# 1-Schematic_power_supply.net
KiCad netlist of a schematic drawn in EasyEDA
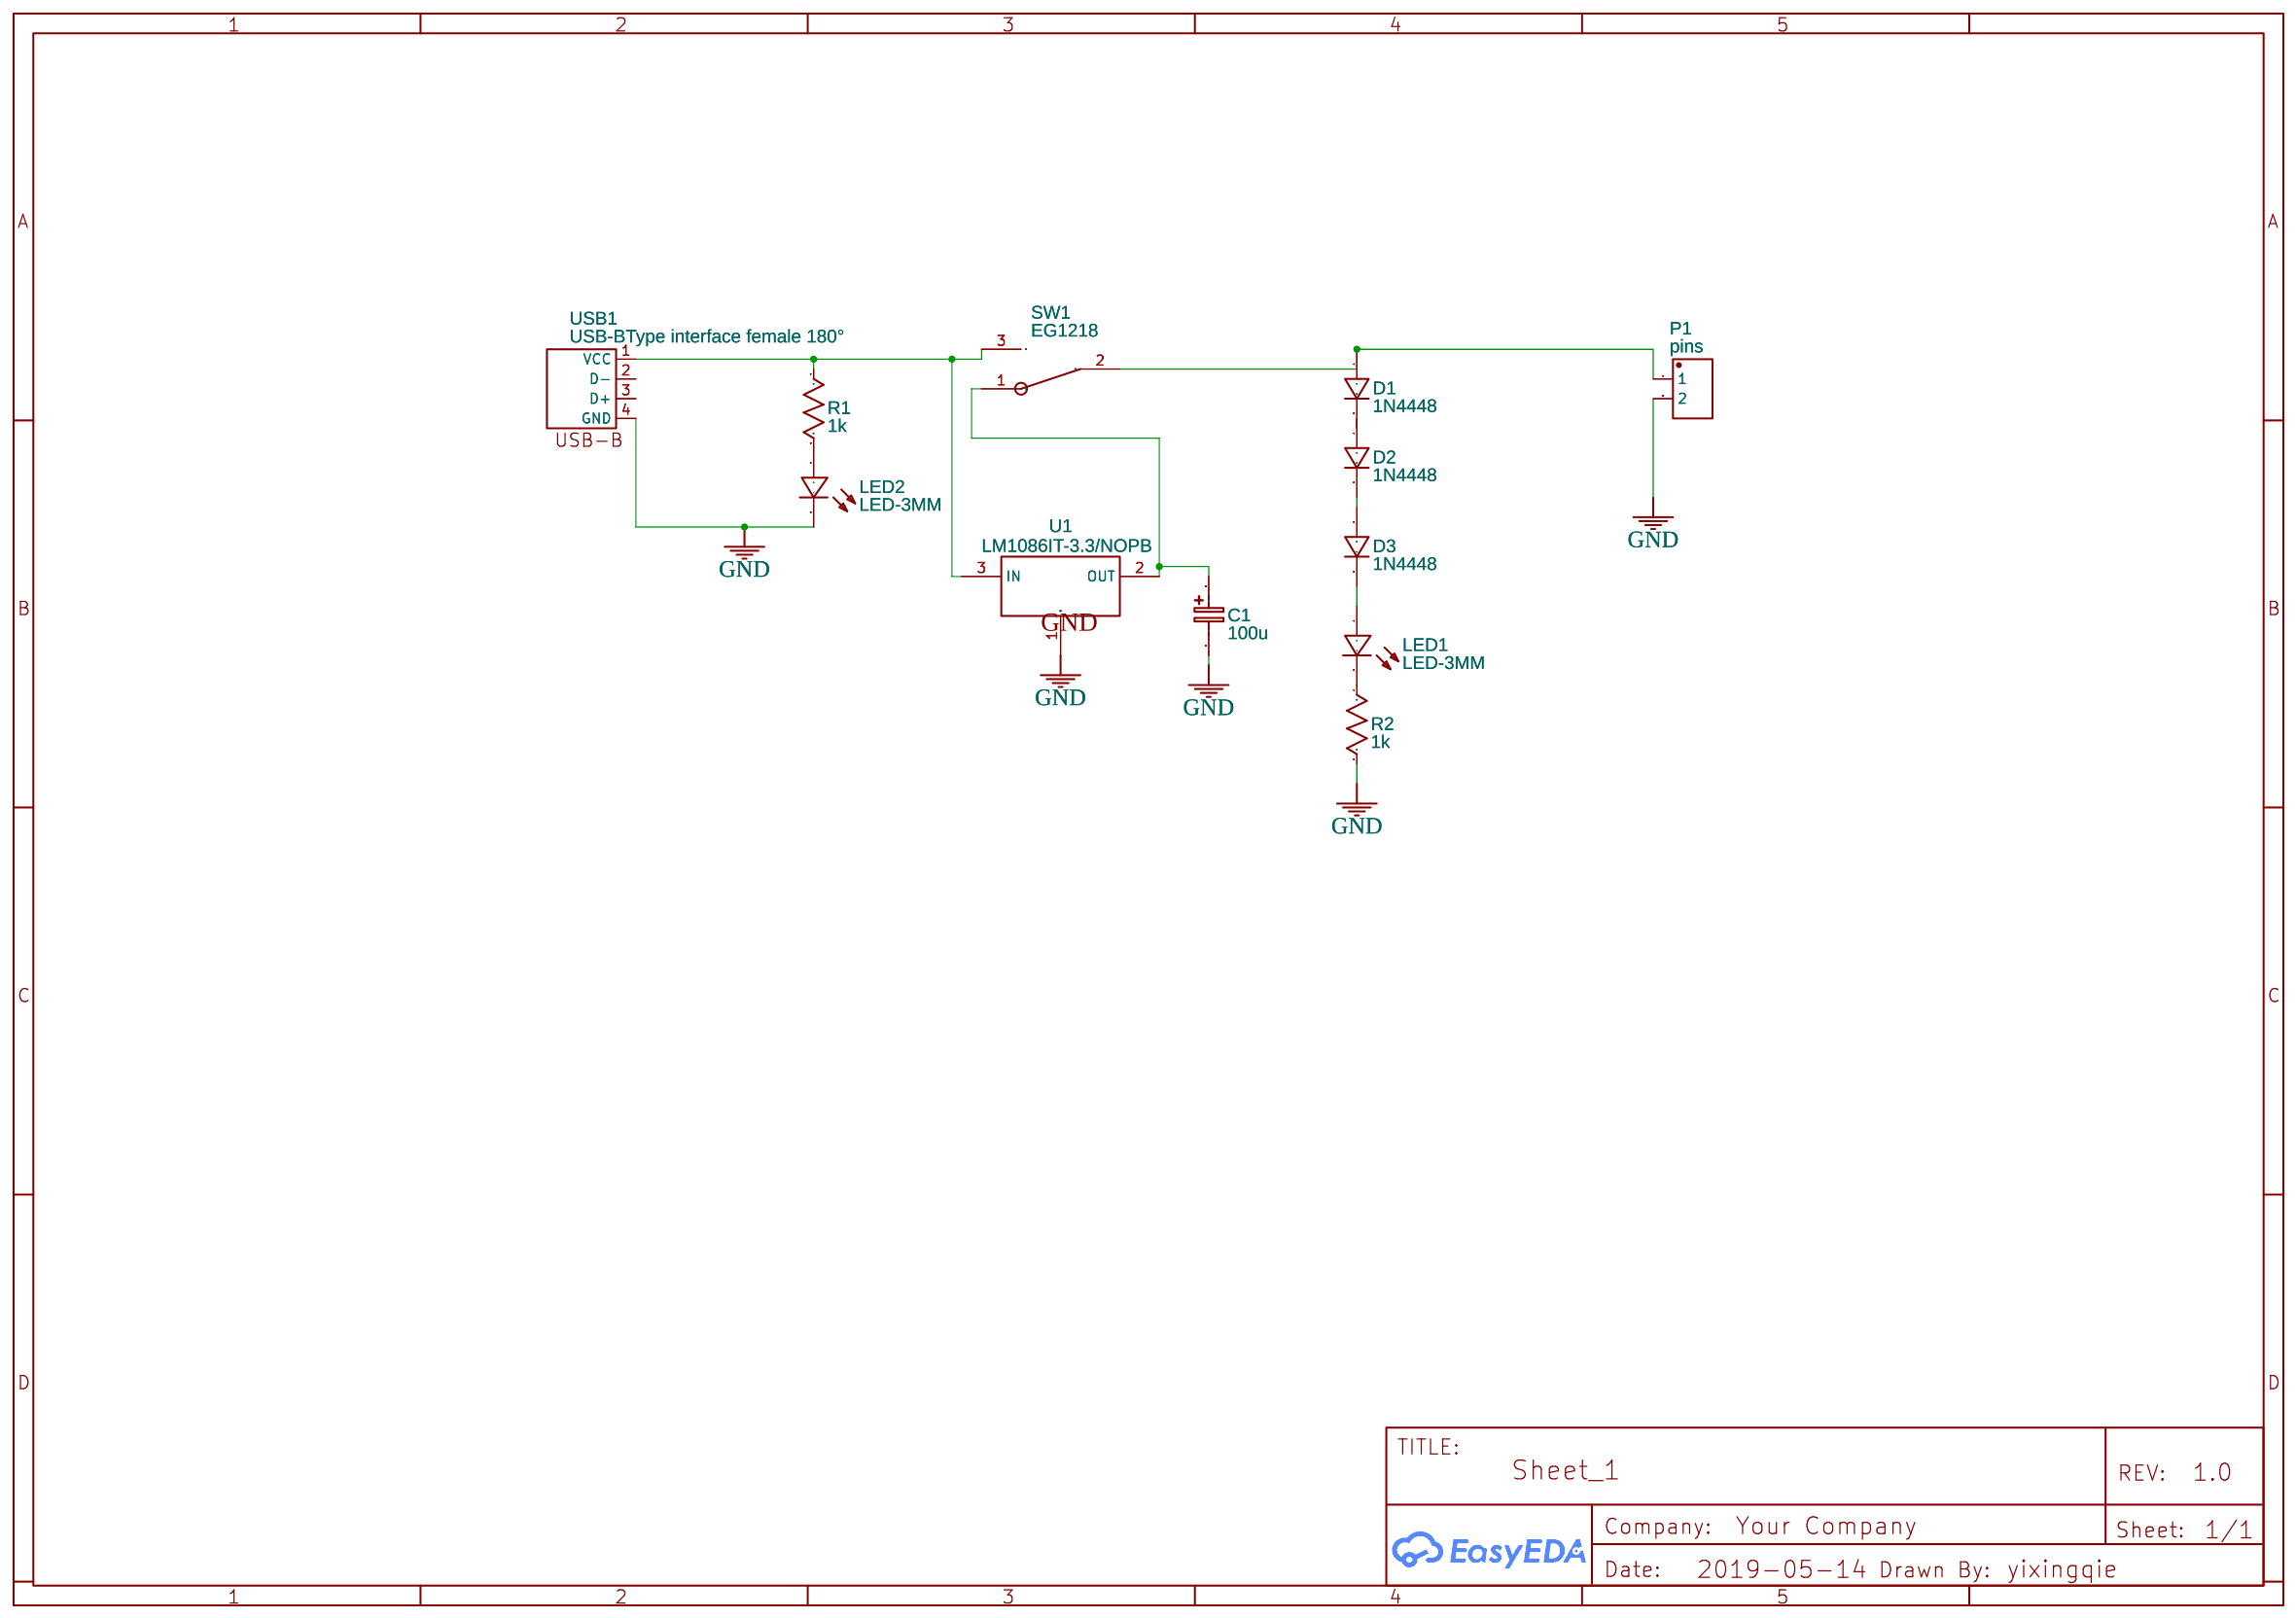
[diagram p0: schematic sheet]

(export (version "E")
  (design (tool "Eeschema 10.0.6"))
  (components
    (comp (ref "C1")
      (value "100u")
      (fields (field (name "BOM_Manufacturer Part") "?"))
      (libsource (lib "") (part "Cap_Electrolytic(TH)_D3.0XF1.5_EU"))
    )
    (comp (ref "D1")
      (value "1N4448")
      (fields (field (name "BOM_Supplier Part") "C54037"))
      (libsource (lib "") (part "Unknown_680_190"))
    )
    (comp (ref "D2")
      (value "1N4448")
      (fields (field (name "BOM_Supplier Part") "C54037"))
      (libsource (lib "") (part "Unknown_680_225"))
    )
    (comp (ref "D3")
      (value "1N4448")
      (fields (field (name "BOM_Supplier Part") "C54037"))
      (libsource (lib "") (part "Unknown_680_270"))
    )
    (comp (ref "LED1")
      (value "LED-3MM")
      (fields
        (field (name "BOM_Manufacturer Part") "204-10SURD/S530-A3")
        (field (name "BOM_Supplier Part") "C99772")
      )
      (libsource (lib "") (part "Unknown_680_320"))
    )
    (comp (ref "LED2")
      (value "LED-3MM")
      (fields
        (field (name "BOM_Manufacturer Part") "204-10SURD/S530-A3")
        (field (name "BOM_Supplier Part") "C99772")
      )
      (libsource (lib "") (part "Unknown_405_240"))
    )
    (comp (ref "P1")
      (value "pins")
      (fields
        (field (name "BOM_Manufacturer Part") "WJ2EDGVC-5.08-2P")
        (field (name "BOM_Supplier Part") "C8445")
      )
      (libsource (lib "") (part "Unknown_845_190"))
    )
    (comp (ref "R1")
      (value "1k")
      (fields (field (name "BOM_Manufacturer Part") "?"))
      (libsource (lib "") (part "Res_AXIAL-0.3(1/8W)_US"))
    )
    (comp (ref "R2")
      (value "1k")
      (fields (field (name "BOM_Manufacturer Part") "?"))
      (libsource (lib "") (part "Res_AXIAL-0.3(1/8W)_US"))
    )
    (comp (ref "SW1")
      (value "EG1218")
      (fields (field (name "BOM_Supplier Part") "C273394"))
      (libsource (lib "") (part "Unknown_520_180"))
    )
    (comp (ref "U1")
      (value "LM1086IT-3.3/NOPB")
      (fields (field (name "BOM_Supplier Part") "C130173"))
      (libsource (lib "") (part "Unknown_530_300"))
    )
    (comp (ref "USB1")
      (value "USB-BType interface female 180°")
      (fields (field (name "BOM_Supplier Part") "C26234"))
      (libsource (lib "") (part "Unknown_290_190"))
    )
  )
  (nets
    (net (code "1") (name "GND") (class "Default")
      (node (ref "C1") (pin "2") (pinfunction "2_2") (pintype "unspecified"))
      (node (ref "LED2") (pin "2") (pinfunction "-_2") (pintype "unspecified"))
      (node (ref "P1") (pin "2") (pinfunction "2_2") (pintype "unspecified"))
      (node (ref "R2") (pin "2") (pinfunction "2_2") (pintype "unspecified"))
      (node (ref "U1") (pin "1") (pinfunction "GND_1") (pintype "passive"))
      (node (ref "USB1") (pin "4") (pinfunction "GND_4") (pintype "input"))
    )
    (net (code "2") (name "Net-(D1-A)") (class "Default")
      (node (ref "D1") (pin "1") (pinfunction "A_1") (pintype "unspecified"))
      (node (ref "P1") (pin "1") (pinfunction "1_1") (pintype "unspecified"))
      (node (ref "SW1") (pin "2") (pinfunction "2_2") (pintype "input"))
    )
    (net (code "3") (name "Net-(D1-K)") (class "Default")
      (node (ref "D1") (pin "2") (pinfunction "K_2") (pintype "unspecified"))
      (node (ref "D2") (pin "1") (pinfunction "A_1") (pintype "unspecified"))
    )
    (net (code "4") (name "Net-(D2-K)") (class "Default")
      (node (ref "D2") (pin "2") (pinfunction "K_2") (pintype "unspecified"))
      (node (ref "D3") (pin "1") (pinfunction "A_1") (pintype "unspecified"))
    )
    (net (code "5") (name "Net-(D3-K)") (class "Default")
      (node (ref "D3") (pin "2") (pinfunction "K_2") (pintype "unspecified"))
      (node (ref "LED1") (pin "1") (pinfunction "+_1") (pintype "unspecified"))
    )
    (net (code "6") (name "Net-(LED1--)") (class "Default")
      (node (ref "LED1") (pin "2") (pinfunction "-_2") (pintype "unspecified"))
      (node (ref "R2") (pin "1") (pinfunction "1_1") (pintype "unspecified"))
    )
    (net (code "7") (name "Net-(LED2-+)") (class "Default")
      (node (ref "LED2") (pin "1") (pinfunction "+_1") (pintype "unspecified"))
      (node (ref "R1") (pin "2") (pinfunction "2_2") (pintype "unspecified"))
    )
    (net (code "8") (name "Net-(U1-IN)") (class "Default")
      (node (ref "R1") (pin "1") (pinfunction "1_1") (pintype "unspecified"))
      (node (ref "SW1") (pin "3") (pinfunction "3_3") (pintype "input"))
      (node (ref "U1") (pin "3") (pinfunction "IN_3") (pintype "passive"))
      (node (ref "USB1") (pin "1") (pinfunction "VCC_1") (pintype "input"))
    )
    (net (code "9") (name "Net-(U1-OUT)") (class "Default")
      (node (ref "C1") (pin "1") (pinfunction "1_1") (pintype "unspecified"))
      (node (ref "SW1") (pin "1") (pinfunction "1_1") (pintype "input"))
      (node (ref "U1") (pin "2") (pinfunction "OUT_2") (pintype "passive"))
    )
    (net (code "10") (name "unconnected-(USB1-D+-Pad3)") (class "Default")
      (node (ref "USB1") (pin "3") (pinfunction "D+_3") (pintype "input"))
    )
    (net (code "11") (name "unconnected-(USB1-D--Pad2)") (class "Default")
      (node (ref "USB1") (pin "2") (pinfunction "D-_2") (pintype "input"))
    )
  )
)
